# mapleCUL_small-V03_012.net
KiCad netlist of a schematic drawn in EAGLE
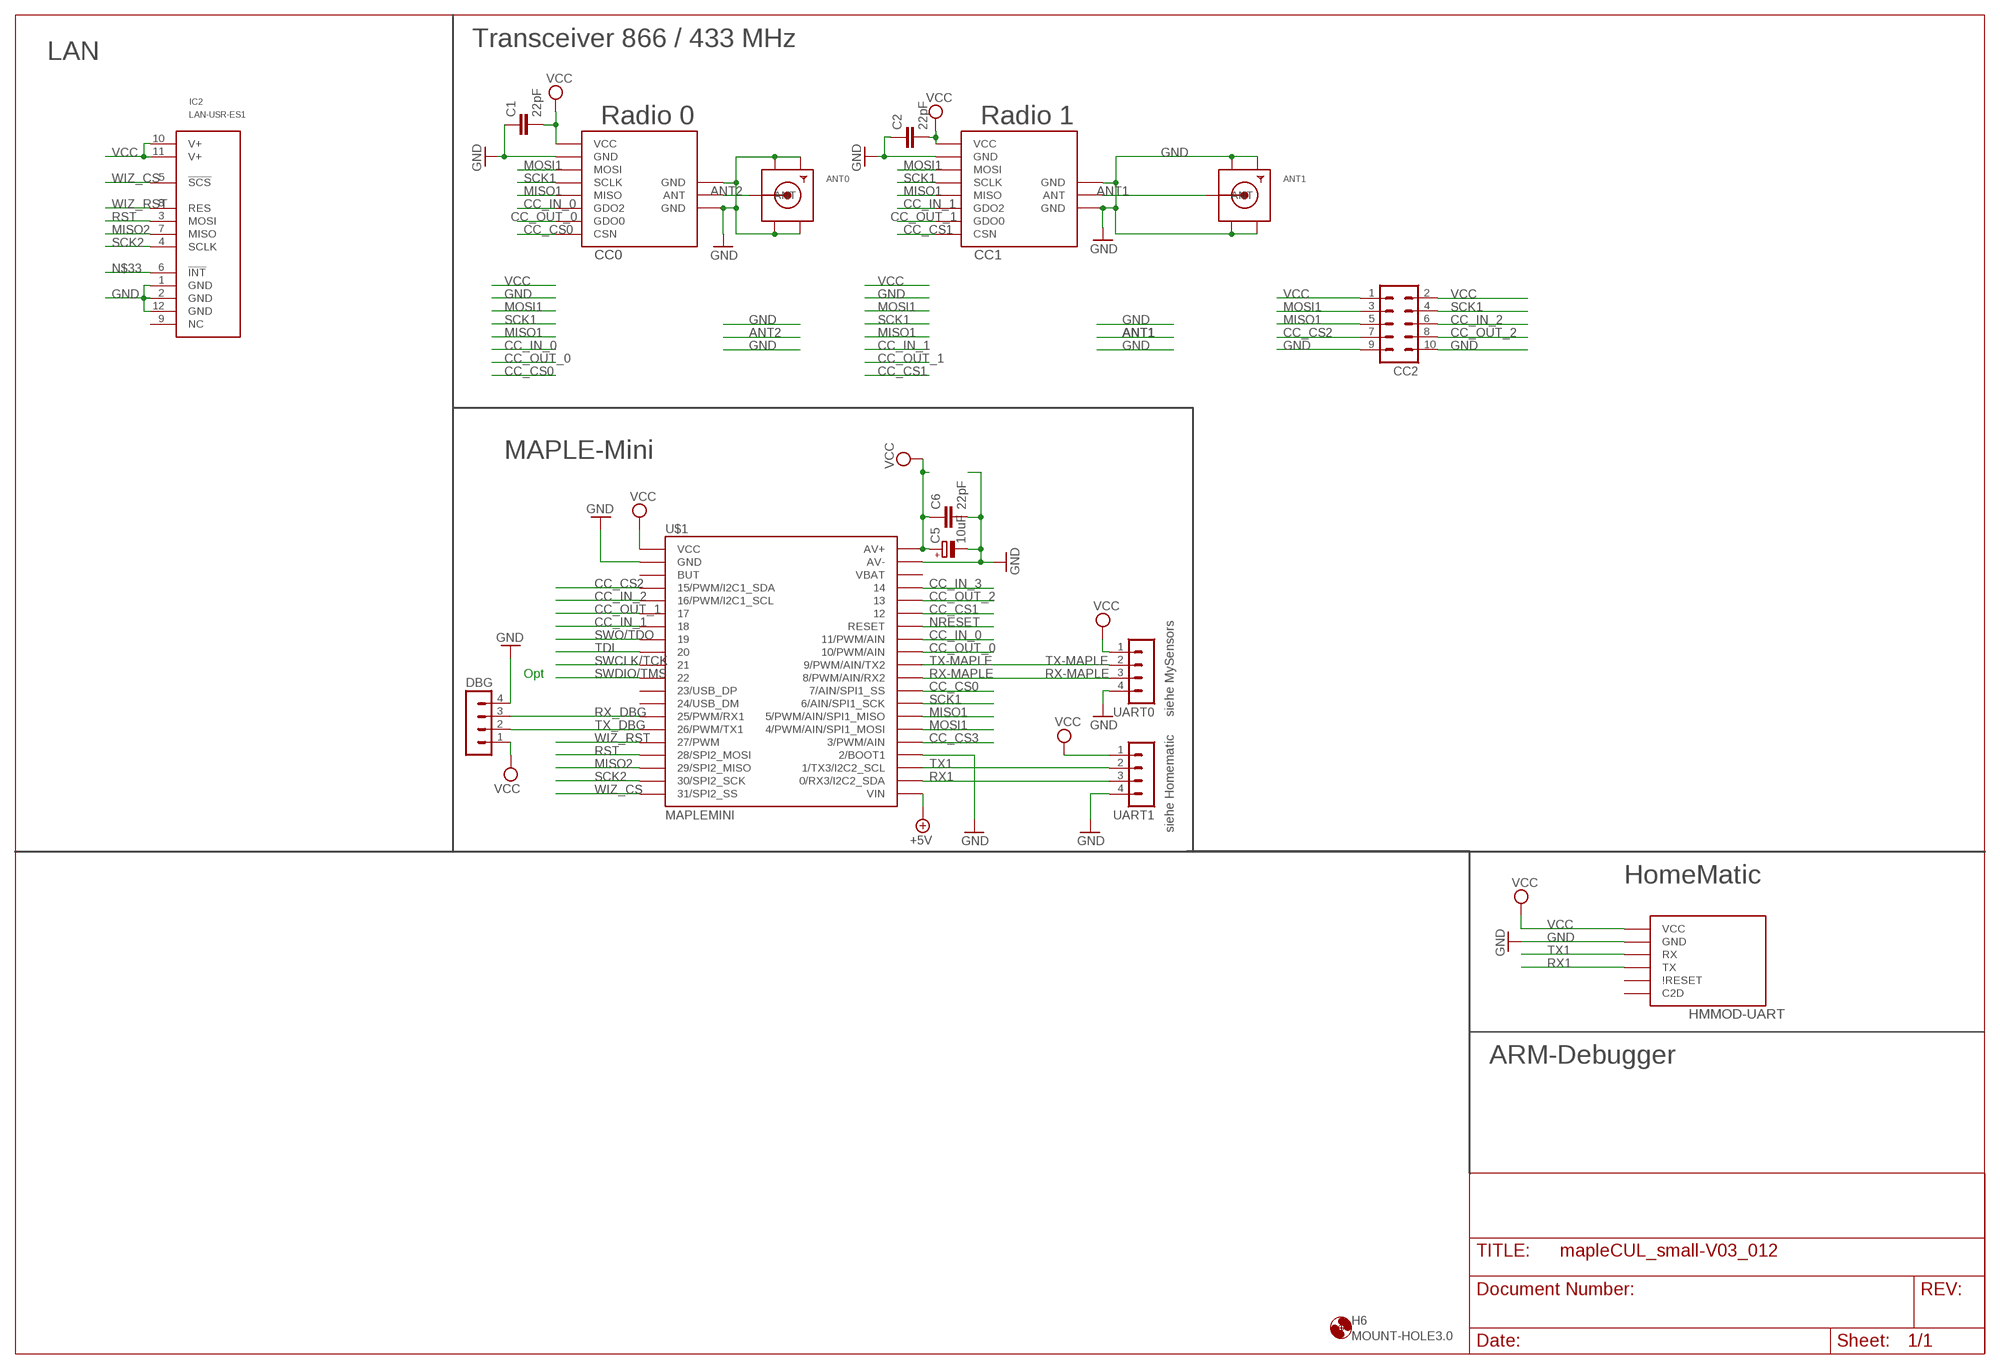
[diagram p0: schematic, sheet 1]

(export (version "E")
  (design (tool "Eeschema 10.0.6"))
  (components
    (comp (ref "ANT0")
      (value "SMACONNECTOR_EDGE_UFL")
      (footprint "eagle-import:SMA_EDGELAUNCH_UFL")
      (libsource (lib "eagle-import") (part "SMACONNECTOR_EDGE_UFL"))
    )
    (comp (ref "ANT1")
      (value "SMACONNECTOR_EDGE_UFL")
      (footprint "eagle-import:SMA_EDGELAUNCH_UFL")
      (libsource (lib "eagle-import") (part "SMACONNECTOR_EDGE_UFL"))
    )
    (comp (ref "C1")
      (value "22pF")
      (footprint "eagle-import:C0805")
      (libsource (lib "eagle-import") (part "C-EUC0805"))
    )
    (comp (ref "C2")
      (value "22pF")
      (footprint "eagle-import:C0805")
      (libsource (lib "eagle-import") (part "C-EUC0805"))
    )
    (comp (ref "C5")
      (value "10uF")
      (footprint "eagle-import:R_2012-12W")
      (libsource (lib "eagle-import") (part "CPOL-EUR/2012-12W"))
    )
    (comp (ref "C6")
      (value "22pF")
      (footprint "eagle-import:C0805")
      (libsource (lib "eagle-import") (part "C-EUC0805"))
    )
    (comp (ref "CC0")
      (value "CC1101")
      (footprint "eagle-import:CC1101_MODULE1_SMD")
      (libsource (lib "eagle-import") (part "CC1101_MODULE1SMD"))
    )
    (comp (ref "CC1")
      (value "CC1101_MODULE1SMD")
      (footprint "eagle-import:CC1101_MODULE1_SMD")
      (libsource (lib "eagle-import") (part "CC1101_MODULE1SMD"))
    )
    (comp (ref "CC2")
      (value "MA05-2")
      (footprint "eagle-import:MA05-2")
      (libsource (lib "eagle-import") (part "MA05-2"))
    )
    (comp (ref "DBG")
      (value "MA04-1")
      (footprint "eagle-import:MA04-1")
      (libsource (lib "eagle-import") (part "MA04-1"))
    )
    (comp (ref "H6")
      (value "MOUNT-HOLE3.0")
      (footprint "eagle-import:3,0")
      (libsource (lib "eagle-import") (part "MOUNT-HOLE3.0"))
    )
    (comp (ref "HMMOD-UART")
      (value "HM-MOD-UARTDIL")
      (footprint "eagle-import:HM-MOD-UART-DIL")
      (libsource (lib "eagle-import") (part "HM-MOD-UARTDIL"))
    )
    (comp (ref "IC2")
      (value "LAN-USR-ES1")
      (footprint "eagle-import:USR-ES1")
      (libsource (lib "eagle-import") (part "LAN-USR-ES1"))
    )
    (comp (ref "U$1")
      (value "MAPLEMINI")
      (footprint "eagle-import:20-DIP")
      (libsource (lib "eagle-import") (part "MAPLEMINI"))
    )
    (comp (ref "UART0")
      (value "MA04-1")
      (footprint "eagle-import:MA04-1")
      (libsource (lib "eagle-import") (part "MA04-1"))
    )
    (comp (ref "UART1")
      (value "MA04-1")
      (footprint "eagle-import:MA04-1")
      (libsource (lib "eagle-import") (part "MA04-1"))
    )
  )
  (nets
    (net (code "1") (name "+5V") (class "Default")
      (node (ref "U$1") (pin "21") (pinfunction "VIN_21") (pintype "bidirectional"))
    )
    (net (code "2") (name "/ANT1") (class "Default")
      (node (ref "ANT1") (pin "P") (pinfunction "ANT_P") (pintype "bidirectional"))
      (node (ref "CC1") (pin "ANT") (pinfunction "ANT_ANT") (pintype "output"))
    )
    (net (code "3") (name "/ANT2") (class "Default")
      (node (ref "ANT0") (pin "P") (pinfunction "ANT_P") (pintype "bidirectional"))
      (node (ref "CC0") (pin "ANT") (pinfunction "ANT_ANT") (pintype "output"))
    )
    (net (code "4") (name "/CC_CS0") (class "Default")
      (node (ref "CC0") (pin "CSN") (pinfunction "CSN_CSN") (pintype "bidirectional"))
      (node (ref "U$1") (pin "29") (pinfunction "7/AIN/SPI1_SS_29") (pintype "bidirectional"))
    )
    (net (code "5") (name "/CC_CS1") (class "Default")
      (node (ref "CC1") (pin "CSN") (pinfunction "CSN_CSN") (pintype "bidirectional"))
      (node (ref "U$1") (pin "35") (pinfunction "12_35") (pintype "bidirectional"))
    )
    (net (code "6") (name "/CC_CS2") (class "Default")
      (node (ref "CC2") (pin "7") (pinfunction "7_7") (pintype "passive"))
      (node (ref "U$1") (pin "4") (pinfunction "15/PWM/I2C1_SDA_4") (pintype "bidirectional"))
    )
    (net (code "7") (name "/CC_CS3") (class "Default")
      (node (ref "U$1") (pin "25") (pinfunction "3/PWM/AIN_25") (pintype "bidirectional"))
    )
    (net (code "8") (name "/CC_IN_0") (class "Default")
      (node (ref "CC0") (pin "GDO2") (pinfunction "GDO2_GDO2") (pintype "bidirectional"))
      (node (ref "U$1") (pin "33") (pinfunction "11/PWM/AIN_33") (pintype "bidirectional"))
    )
    (net (code "9") (name "/CC_IN_1") (class "Default")
      (node (ref "CC1") (pin "GDO2") (pinfunction "GDO2_GDO2") (pintype "bidirectional"))
      (node (ref "U$1") (pin "7") (pinfunction "18_7") (pintype "bidirectional"))
    )
    (net (code "10") (name "/CC_IN_2") (class "Default")
      (node (ref "CC2") (pin "6") (pinfunction "6_6") (pintype "passive"))
      (node (ref "U$1") (pin "5") (pinfunction "16/PWM/I2C1_SCL_5") (pintype "bidirectional"))
    )
    (net (code "11") (name "/CC_IN_3") (class "Default")
      (node (ref "U$1") (pin "37") (pinfunction "14_37") (pintype "bidirectional"))
    )
    (net (code "12") (name "/CC_OUT_0") (class "Default")
      (node (ref "CC0") (pin "GDO0") (pinfunction "GDO0_GDO0") (pintype "bidirectional"))
      (node (ref "U$1") (pin "32") (pinfunction "10/PWM/AIN_32") (pintype "bidirectional"))
    )
    (net (code "13") (name "/CC_OUT_1") (class "Default")
      (node (ref "CC1") (pin "GDO0") (pinfunction "GDO0_GDO0") (pintype "bidirectional"))
      (node (ref "U$1") (pin "6") (pinfunction "17_6") (pintype "bidirectional"))
    )
    (net (code "14") (name "/CC_OUT_2") (class "Default")
      (node (ref "CC2") (pin "8") (pinfunction "8_8") (pintype "passive"))
      (node (ref "U$1") (pin "36") (pinfunction "13_36") (pintype "bidirectional"))
    )
    (net (code "15") (name "/MISO1") (class "Default")
      (node (ref "CC0") (pin "MISO") (pinfunction "MISO_MISO") (pintype "bidirectional"))
      (node (ref "CC1") (pin "MISO") (pinfunction "MISO_MISO") (pintype "bidirectional"))
      (node (ref "CC2") (pin "5") (pinfunction "5_5") (pintype "passive"))
      (node (ref "U$1") (pin "27") (pinfunction "5/PWM/AIN/SPI1_MISO_27") (pintype "bidirectional"))
    )
    (net (code "16") (name "/MISO2") (class "Default")
      (node (ref "IC2") (pin "7") (pinfunction "MISO_7") (pintype "bidirectional"))
      (node (ref "U$1") (pin "18") (pinfunction "29/SPI2_MISO_18") (pintype "bidirectional"))
    )
    (net (code "17") (name "/MOSI1") (class "Default")
      (node (ref "CC0") (pin "MOSI") (pinfunction "MOSI_MOSI") (pintype "bidirectional"))
      (node (ref "CC1") (pin "MOSI") (pinfunction "MOSI_MOSI") (pintype "bidirectional"))
      (node (ref "CC2") (pin "3") (pinfunction "3_3") (pintype "passive"))
      (node (ref "U$1") (pin "26") (pinfunction "4/PWM/AIN/SPI1_MOSI_26") (pintype "bidirectional"))
    )
    (net (code "18") (name "/N$33") (class "Default")
      (node (ref "IC2") (pin "6") (pinfunction "~{INT}_6") (pintype "output"))
    )
    (net (code "19") (name "/NRESET") (class "Default")
      (node (ref "U$1") (pin "34") (pinfunction "RESET_34") (pintype "bidirectional"))
    )
    (net (code "20") (name "/RST") (class "Default")
      (node (ref "IC2") (pin "3") (pinfunction "MOSI_3") (pintype "bidirectional"))
      (node (ref "U$1") (pin "17") (pinfunction "28/SPI2_MOSI_17") (pintype "bidirectional"))
    )
    (net (code "21") (name "/RX-MAPLE") (class "Default")
      (node (ref "U$1") (pin "30") (pinfunction "8/PWM/AIN/RX2_30") (pintype "bidirectional"))
      (node (ref "UART0") (pin "3") (pinfunction "3_3") (pintype "passive"))
    )
    (net (code "22") (name "/RX1") (class "Default")
      (node (ref "HMMOD-UART") (pin "5") (pinfunction "TX_5") (pintype "bidirectional"))
      (node (ref "U$1") (pin "22") (pinfunction "0/RX3/I2C2_SDA_22") (pintype "bidirectional"))
      (node (ref "UART1") (pin "3") (pinfunction "3_3") (pintype "passive"))
    )
    (net (code "23") (name "/RX_DBG") (class "Default")
      (node (ref "DBG") (pin "3") (pinfunction "3_3") (pintype "passive"))
      (node (ref "U$1") (pin "14") (pinfunction "25/PWM/RX1_14") (pintype "bidirectional"))
    )
    (net (code "24") (name "/SCK1") (class "Default")
      (node (ref "CC0") (pin "SCLK") (pinfunction "SCLK_SCLK") (pintype "bidirectional"))
      (node (ref "CC1") (pin "SCLK") (pinfunction "SCLK_SCLK") (pintype "bidirectional"))
      (node (ref "CC2") (pin "4") (pinfunction "4_4") (pintype "passive"))
      (node (ref "U$1") (pin "28") (pinfunction "6/AIN/SPI1_SCK_28") (pintype "bidirectional"))
    )
    (net (code "25") (name "/SCK2") (class "Default")
      (node (ref "IC2") (pin "4") (pinfunction "SCLK_4") (pintype "input"))
      (node (ref "U$1") (pin "19") (pinfunction "30/SPI2_SCK_19") (pintype "bidirectional"))
    )
    (net (code "26") (name "/SWCLK{slash}TCK") (class "Default")
      (node (ref "U$1") (pin "10") (pinfunction "21_10") (pintype "bidirectional"))
    )
    (net (code "27") (name "/SWDIO{slash}TMS") (class "Default")
      (node (ref "U$1") (pin "11") (pinfunction "22_11") (pintype "bidirectional"))
    )
    (net (code "28") (name "/SWO{slash}TDO") (class "Default")
      (node (ref "U$1") (pin "8") (pinfunction "19_8") (pintype "bidirectional"))
    )
    (net (code "29") (name "/TDI") (class "Default")
      (node (ref "U$1") (pin "9") (pinfunction "20_9") (pintype "bidirectional"))
    )
    (net (code "30") (name "/TX-MAPLE") (class "Default")
      (node (ref "U$1") (pin "31") (pinfunction "9/PWM/AIN/TX2_31") (pintype "bidirectional"))
      (node (ref "UART0") (pin "2") (pinfunction "2_2") (pintype "passive"))
    )
    (net (code "31") (name "/TX1") (class "Default")
      (node (ref "HMMOD-UART") (pin "6") (pinfunction "RX_6") (pintype "bidirectional"))
      (node (ref "U$1") (pin "23") (pinfunction "1/TX3/I2C2_SCL_23") (pintype "bidirectional"))
      (node (ref "UART1") (pin "2") (pinfunction "2_2") (pintype "passive"))
    )
    (net (code "32") (name "/TX_DBG") (class "Default")
      (node (ref "DBG") (pin "2") (pinfunction "2_2") (pintype "passive"))
      (node (ref "U$1") (pin "15") (pinfunction "26/PWM/TX1_15") (pintype "bidirectional"))
    )
    (net (code "33") (name "/WIZ_CS") (class "Default")
      (node (ref "IC2") (pin "5") (pinfunction "~{SCS}_5") (pintype "input"))
      (node (ref "U$1") (pin "20") (pinfunction "31/SPI2_SS_20") (pintype "bidirectional"))
    )
    (net (code "34") (name "/WIZ_RST") (class "Default")
      (node (ref "IC2") (pin "8") (pinfunction "RES_8") (pintype "input"))
      (node (ref "U$1") (pin "16") (pinfunction "27/PWM_16") (pintype "bidirectional"))
    )
    (net (code "35") (name "GND") (class "Default")
      (node (ref "ANT0") (pin "GND@1") (pinfunction "GND1_GND@1") (pintype "power_in"))
      (node (ref "ANT0") (pin "GND@2") (pinfunction "GND2_GND@2") (pintype "power_in"))
      (node (ref "ANT0") (pin "GND@3") (pinfunction "GND3_GND@3") (pintype "power_in"))
      (node (ref "ANT0") (pin "GND@4") (pinfunction "GND4_GND@4") (pintype "power_in"))
      (node (ref "ANT1") (pin "GND@1") (pinfunction "GND1_GND@1") (pintype "power_in"))
      (node (ref "ANT1") (pin "GND@2") (pinfunction "GND2_GND@2") (pintype "power_in"))
      (node (ref "ANT1") (pin "GND@3") (pinfunction "GND3_GND@3") (pintype "power_in"))
      (node (ref "ANT1") (pin "GND@4") (pinfunction "GND4_GND@4") (pintype "power_in"))
      (node (ref "C1") (pin "1") (pinfunction "1_1") (pintype "passive"))
      (node (ref "C2") (pin "1") (pinfunction "1_1") (pintype "passive"))
      (node (ref "C5") (pin "-") (pinfunction "-_-") (pintype "passive"))
      (node (ref "C6") (pin "2") (pinfunction "2_2") (pintype "passive"))
      (node (ref "CC0") (pin "GND@0") (pinfunction "GND_GND@0") (pintype "power_in"))
      (node (ref "CC0") (pin "GND@1") (pinfunction "GND_GND@1") (pintype "power_in"))
      (node (ref "CC0") (pin "GND@2") (pinfunction "GND_GND@2") (pintype "power_in"))
      (node (ref "CC1") (pin "GND@0") (pinfunction "GND_GND@0") (pintype "power_in"))
      (node (ref "CC1") (pin "GND@1") (pinfunction "GND_GND@1") (pintype "power_in"))
      (node (ref "CC1") (pin "GND@2") (pinfunction "GND_GND@2") (pintype "power_in"))
      (node (ref "CC2") (pin "10") (pinfunction "10_10") (pintype "passive"))
      (node (ref "CC2") (pin "9") (pinfunction "9_9") (pintype "passive"))
      (node (ref "DBG") (pin "4") (pinfunction "4_4") (pintype "passive"))
      (node (ref "HMMOD-UART") (pin "2") (pinfunction "GND_2") (pintype "power_in"))
      (node (ref "IC2") (pin "1") (pinfunction "GND_1") (pintype "power_in"))
      (node (ref "IC2") (pin "12") (pinfunction "GND_12") (pintype "power_in"))
      (node (ref "IC2") (pin "2") (pinfunction "GND_2") (pintype "power_in"))
      (node (ref "U$1") (pin "2") (pinfunction "GND_2") (pintype "bidirectional"))
      (node (ref "U$1") (pin "24") (pinfunction "2/BOOT1_24") (pintype "bidirectional"))
      (node (ref "U$1") (pin "39") (pinfunction "AV-_39") (pintype "bidirectional"))
      (node (ref "UART0") (pin "4") (pinfunction "4_4") (pintype "passive"))
      (node (ref "UART1") (pin "4") (pinfunction "4_4") (pintype "passive"))
    )
    (net (code "36") (name "VCC") (class "Default")
      (node (ref "C1") (pin "2") (pinfunction "2_2") (pintype "passive"))
      (node (ref "C2") (pin "2") (pinfunction "2_2") (pintype "passive"))
      (node (ref "C5") (pin "+") (pinfunction "+_+") (pintype "passive"))
      (node (ref "C6") (pin "1") (pinfunction "1_1") (pintype "passive"))
      (node (ref "CC0") (pin "VCC") (pinfunction "VCC_VCC") (pintype "power_in"))
      (node (ref "CC1") (pin "VCC") (pinfunction "VCC_VCC") (pintype "power_in"))
      (node (ref "CC2") (pin "1") (pinfunction "1_1") (pintype "passive"))
      (node (ref "CC2") (pin "2") (pinfunction "2_2") (pintype "passive"))
      (node (ref "DBG") (pin "1") (pinfunction "1_1") (pintype "passive"))
      (node (ref "HMMOD-UART") (pin "1") (pinfunction "VCC_1") (pintype "power_in"))
      (node (ref "IC2") (pin "10") (pinfunction "V+_10") (pintype "power_in"))
      (node (ref "IC2") (pin "11") (pinfunction "V+_11") (pintype "power_in"))
      (node (ref "U$1") (pin "1") (pinfunction "VCC_1") (pintype "bidirectional"))
      (node (ref "U$1") (pin "40") (pinfunction "AV+_40") (pintype "bidirectional"))
      (node (ref "UART0") (pin "1") (pinfunction "1_1") (pintype "passive"))
      (node (ref "UART1") (pin "1") (pinfunction "1_1") (pintype "passive"))
    )
    (net (code "37") (name "unconnected-(HMMOD-UART-C2D-Pad3)") (class "Default")
      (node (ref "HMMOD-UART") (pin "3") (pinfunction "C2D_3") (pintype "bidirectional"))
    )
    (net (code "38") (name "unconnected-(HMMOD-UART-\\~{RESET}-Pad4)") (class "Default")
      (node (ref "HMMOD-UART") (pin "4") (pinfunction "\\~{RESET}_4") (pintype "bidirectional"))
    )
    (net (code "39") (name "unconnected-(IC2-NC-Pad9)") (class "Default")
      (node (ref "IC2") (pin "9") (pinfunction "NC_9") (pintype "no_connect"))
    )
    (net (code "40") (name "unconnected-(U$1-23{slash}USB_DP-Pad12)") (class "Default")
      (node (ref "U$1") (pin "12") (pinfunction "23/USB_DP_12") (pintype "bidirectional"))
    )
    (net (code "41") (name "unconnected-(U$1-24{slash}USB_DM-Pad13)") (class "Default")
      (node (ref "U$1") (pin "13") (pinfunction "24/USB_DM_13") (pintype "bidirectional"))
    )
    (net (code "42") (name "unconnected-(U$1-BUT-Pad3)") (class "Default")
      (node (ref "U$1") (pin "3") (pinfunction "BUT_3") (pintype "bidirectional"))
    )
    (net (code "43") (name "unconnected-(U$1-VBAT-Pad38)") (class "Default")
      (node (ref "U$1") (pin "38") (pinfunction "VBAT_38") (pintype "bidirectional"))
    )
  )
)
